# einstein_v1_1.net
KiCad netlist of a schematic drawn in EAGLE
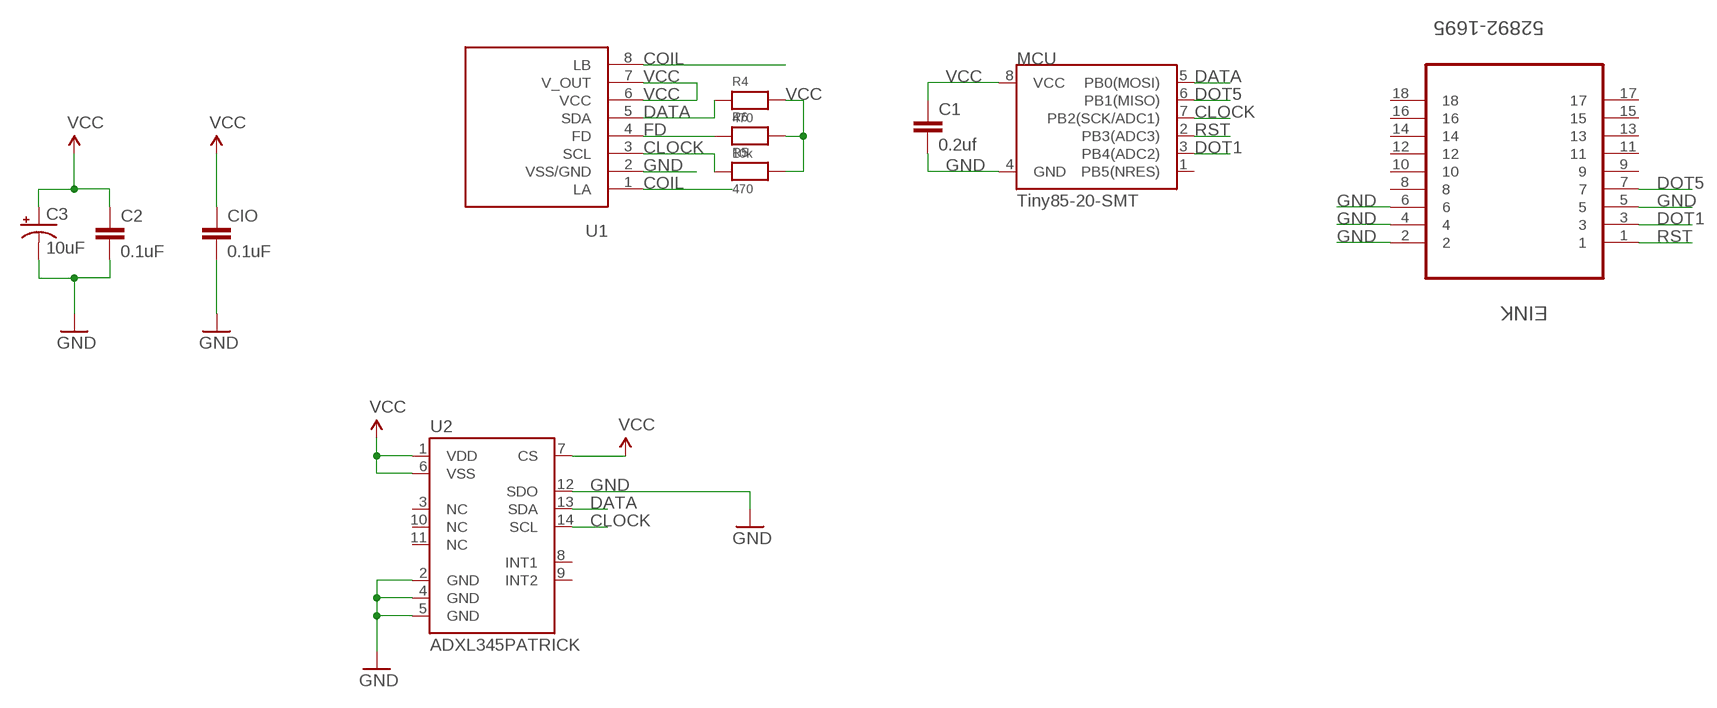
[diagram p0: schematic, sheet 1]

(export (version "E")
  (design (tool "Eeschema 10.0.6"))
  (components
    (comp (ref "C1")
      (value "0.2uf")
      (footprint "eagle-import:1206")
      (libsource (lib "eagle-import") (part "CAP1206"))
    )
    (comp (ref "C2")
      (value "0.1uF")
      (footprint "eagle-import:0603-CAP")
      (libsource (lib "eagle-import") (part "CAP0603-CAP"))
    )
    (comp (ref "C3")
      (value "10uF")
      (footprint "eagle-import:EIA3216")
      (libsource (lib "eagle-import") (part "CAP_POL1206"))
    )
    (comp (ref "CIO")
      (value "0.1uF")
      (footprint "eagle-import:0603-CAP")
      (libsource (lib "eagle-import") (part "CAP0603-CAP"))
    )
    (comp (ref "EINK")
      (value "52892-1695")
      (footprint "eagle-import:MOLEX_52892-1695")
      (libsource (lib "eagle-import") (part "52892-1695"))
    )
    (comp (ref "MCU")
      (value "Tiny85-20-SMT")
      (footprint "eagle-import:SO08-EIAJ")
      (libsource (lib "eagle-import") (part "ATTINY45TINY85-20-SMT"))
    )
    (comp (ref "R4")
      (value "470")
      (footprint "eagle-import:0603")
      (libsource (lib "eagle-import") (part "RESISTOR0603"))
    )
    (comp (ref "R5")
      (value "470")
      (footprint "eagle-import:0603")
      (libsource (lib "eagle-import") (part "RESISTOR0603"))
    )
    (comp (ref "R6")
      (value "10k")
      (footprint "eagle-import:0603")
      (libsource (lib "eagle-import") (part "RESISTOR0603"))
    )
    (comp (ref "U1")
      (value "NT3H1101")
      (footprint "eagle-import:NT3H1101")
      (libsource (lib "eagle-import") (part "NT3H1101"))
    )
    (comp (ref "U2")
      (value "ADXL345PATRICK")
      (footprint "eagle-import:LGA14_1_1_PATRICK")
      (libsource (lib "eagle-import") (part "ADXL345PATRICK"))
    )
  )
  (nets
    (net (code "1") (name "/CLOCK") (class "Default")
      (node (ref "MCU") (pin "7") (pinfunction "PB2(SCK/ADC1)_7") (pintype "bidirectional"))
      (node (ref "R5") (pin "1") (pinfunction "1_1") (pintype "passive"))
      (node (ref "U1") (pin "3") (pinfunction "SCL_3") (pintype "bidirectional"))
      (node (ref "U2") (pin "14") (pinfunction "SCL_14") (pintype "bidirectional"))
    )
    (net (code "2") (name "/COIL") (class "Default")
      (node (ref "U1") (pin "1") (pinfunction "LA_1") (pintype "bidirectional"))
      (node (ref "U1") (pin "8") (pinfunction "LB_8") (pintype "bidirectional"))
    )
    (net (code "3") (name "/DATA") (class "Default")
      (node (ref "MCU") (pin "5") (pinfunction "PB0(MOSI)_5") (pintype "bidirectional"))
      (node (ref "R4") (pin "1") (pinfunction "1_1") (pintype "passive"))
      (node (ref "U1") (pin "5") (pinfunction "SDA_5") (pintype "bidirectional"))
      (node (ref "U2") (pin "13") (pinfunction "SDA_13") (pintype "bidirectional"))
    )
    (net (code "4") (name "/DOT1") (class "Default")
      (node (ref "EINK") (pin "3") (pinfunction "3_3") (pintype "passive"))
      (node (ref "MCU") (pin "3") (pinfunction "PB4(ADC2)_3") (pintype "bidirectional"))
    )
    (net (code "5") (name "/DOT5") (class "Default")
      (node (ref "EINK") (pin "7") (pinfunction "7_7") (pintype "passive"))
      (node (ref "MCU") (pin "6") (pinfunction "PB1(MISO)_6") (pintype "bidirectional"))
    )
    (net (code "6") (name "/FD") (class "Default")
      (node (ref "R6") (pin "1") (pinfunction "1_1") (pintype "passive"))
      (node (ref "U1") (pin "4") (pinfunction "FD_4") (pintype "bidirectional"))
    )
    (net (code "7") (name "/RST") (class "Default")
      (node (ref "EINK") (pin "1") (pinfunction "1_1") (pintype "passive"))
      (node (ref "MCU") (pin "2") (pinfunction "PB3(ADC3)_2") (pintype "bidirectional"))
    )
    (net (code "8") (name "GND") (class "Default")
      (node (ref "C1") (pin "2") (pinfunction "2_2") (pintype "passive"))
      (node (ref "C2") (pin "2") (pinfunction "2_2") (pintype "passive"))
      (node (ref "C3") (pin "C") (pinfunction "-_C") (pintype "passive"))
      (node (ref "CIO") (pin "2") (pinfunction "2_2") (pintype "passive"))
      (node (ref "EINK") (pin "2") (pinfunction "2_2") (pintype "passive"))
      (node (ref "EINK") (pin "4") (pinfunction "4_4") (pintype "passive"))
      (node (ref "EINK") (pin "5") (pinfunction "5_5") (pintype "passive"))
      (node (ref "EINK") (pin "6") (pinfunction "6_6") (pintype "passive"))
      (node (ref "MCU") (pin "4") (pinfunction "GND_4") (pintype "bidirectional"))
      (node (ref "U1") (pin "2") (pinfunction "VSS/GND_2") (pintype "power_in"))
      (node (ref "U2") (pin "12") (pinfunction "SDO_12") (pintype "bidirectional"))
      (node (ref "U2") (pin "2") (pinfunction "GND_2") (pintype "bidirectional"))
      (node (ref "U2") (pin "4") (pinfunction "GND_4") (pintype "bidirectional"))
      (node (ref "U2") (pin "5") (pinfunction "GND_5") (pintype "bidirectional"))
    )
    (net (code "9") (name "VCC") (class "Default")
      (node (ref "C1") (pin "1") (pinfunction "1_1") (pintype "passive"))
      (node (ref "C2") (pin "1") (pinfunction "1_1") (pintype "passive"))
      (node (ref "C3") (pin "A") (pinfunction "+_A") (pintype "passive"))
      (node (ref "CIO") (pin "1") (pinfunction "1_1") (pintype "passive"))
      (node (ref "MCU") (pin "8") (pinfunction "VCC_8") (pintype "bidirectional"))
      (node (ref "R4") (pin "2") (pinfunction "2_2") (pintype "passive"))
      (node (ref "R5") (pin "2") (pinfunction "2_2") (pintype "passive"))
      (node (ref "R6") (pin "2") (pinfunction "2_2") (pintype "passive"))
      (node (ref "U1") (pin "6") (pinfunction "VCC_6") (pintype "power_in"))
      (node (ref "U1") (pin "7") (pinfunction "V_OUT_7") (pintype "power_in"))
      (node (ref "U2") (pin "1") (pinfunction "VDD_1") (pintype "bidirectional"))
      (node (ref "U2") (pin "6") (pinfunction "VSS_6") (pintype "bidirectional"))
      (node (ref "U2") (pin "7") (pinfunction "CS_7") (pintype "bidirectional"))
    )
    (net (code "10") (name "unconnected-(EINK-Pad8)") (class "Default")
      (node (ref "EINK") (pin "8") (pinfunction "8_8") (pintype "passive"))
    )
    (net (code "11") (name "unconnected-(EINK-Pad9)") (class "Default")
      (node (ref "EINK") (pin "9") (pinfunction "9_9") (pintype "passive"))
    )
    (net (code "12") (name "unconnected-(EINK-Pad10)") (class "Default")
      (node (ref "EINK") (pin "10") (pinfunction "10_10") (pintype "passive"))
    )
    (net (code "13") (name "unconnected-(EINK-Pad11)") (class "Default")
      (node (ref "EINK") (pin "11") (pinfunction "11_11") (pintype "passive"))
    )
    (net (code "14") (name "unconnected-(EINK-Pad12)") (class "Default")
      (node (ref "EINK") (pin "12") (pinfunction "12_12") (pintype "passive"))
    )
    (net (code "15") (name "unconnected-(EINK-Pad13)") (class "Default")
      (node (ref "EINK") (pin "13") (pinfunction "13_13") (pintype "passive"))
    )
    (net (code "16") (name "unconnected-(EINK-Pad14)") (class "Default")
      (node (ref "EINK") (pin "14") (pinfunction "14_14") (pintype "passive"))
    )
    (net (code "17") (name "unconnected-(EINK-Pad15)") (class "Default")
      (node (ref "EINK") (pin "15") (pinfunction "15_15") (pintype "passive"))
    )
    (net (code "18") (name "unconnected-(EINK-Pad16)") (class "Default")
      (node (ref "EINK") (pin "16") (pinfunction "16_16") (pintype "passive"))
    )
    (net (code "19") (name "unconnected-(EINK-Pad17)") (class "Default")
      (node (ref "EINK") (pin "17") (pinfunction "17_17") (pintype "passive"))
    )
    (net (code "20") (name "unconnected-(EINK-Pad18)") (class "Default")
      (node (ref "EINK") (pin "18") (pinfunction "18_18") (pintype "passive"))
    )
    (net (code "21") (name "unconnected-(MCU-PB5(NRES)-Pad1)") (class "Default")
      (node (ref "MCU") (pin "1") (pinfunction "PB5(NRES)_1") (pintype "bidirectional"))
    )
    (net (code "22") (name "unconnected-(U2-INT1-Pad8)") (class "Default")
      (node (ref "U2") (pin "8") (pinfunction "INT1_8") (pintype "bidirectional"))
    )
    (net (code "23") (name "unconnected-(U2-INT2-Pad9)") (class "Default")
      (node (ref "U2") (pin "9") (pinfunction "INT2_9") (pintype "bidirectional"))
    )
    (net (code "24") (name "unconnected-(U2-NC-Pad3)") (class "Default")
      (node (ref "U2") (pin "3") (pinfunction "NC_3") (pintype "bidirectional"))
    )
    (net (code "25") (name "unconnected-(U2-NC-Pad10)") (class "Default")
      (node (ref "U2") (pin "10") (pinfunction "NC_10") (pintype "bidirectional"))
    )
    (net (code "26") (name "unconnected-(U2-NC-Pad11)") (class "Default")
      (node (ref "U2") (pin "11") (pinfunction "NC_11") (pintype "bidirectional"))
    )
  )
)
